# d1-mini-onboard.net
KiCad netlist of a schematic drawn in EAGLE
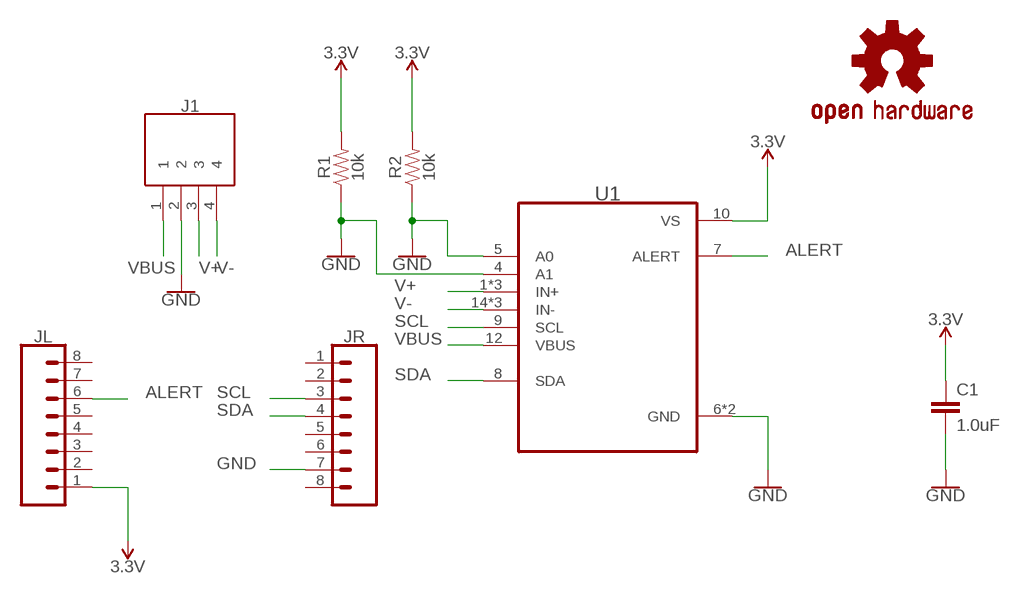
[diagram p0: schematic, sheet 1]

(export (version "E")
  (design (tool "Eeschema 10.0.6"))
  (components
    (comp (ref "C1")
      (value "1.0uF")
      (footprint "eagle-import:1206")
      (libsource (lib "eagle-import") (part "1.0UF-1206-50V-10%"))
    )
    (comp (ref "J1")
      (value "282834-4")
      (footprint "eagle-import:2828344")
      (fields (field (name "MOUSER_PART_NUMBER") "571-282834-4"))
      (libsource (lib "eagle-import") (part "282834-4"))
    )
    (comp (ref "JL")
      (value "CONN_08NO_SILK_FEMALE_PTH")
      (footprint "eagle-import:1X08_NO_SILK")
      (libsource (lib "eagle-import") (part "CONN_08NO_SILK_FEMALE_PTH"))
    )
    (comp (ref "JR")
      (value "CONN_08NO_SILK_FEMALE_PTH")
      (footprint "eagle-import:1X08_NO_SILK")
      (libsource (lib "eagle-import") (part "CONN_08NO_SILK_FEMALE_PTH"))
    )
    (comp (ref "LOGO1")
      (value "OSHW-LOGOS")
      (footprint "eagle-import:OSHW-LOGO-S")
      (libsource (lib "eagle-import") (part "OSHW-LOGOS"))
    )
    (comp (ref "R1")
      (value "10k")
      (footprint "eagle-import:1206")
      (libsource (lib "eagle-import") (part "RESISTOR1206"))
    )
    (comp (ref "R2")
      (value "10k")
      (footprint "eagle-import:1206")
      (libsource (lib "eagle-import") (part "RESISTOR1206"))
    )
    (comp (ref "U1")
      (value "INA260AIPWR")
      (footprint "eagle-import:SOP65P640X120-16N")
      (fields (field (name "MF") "Texas Instruments"))
      (libsource (lib "eagle-import") (part "INA260AIPWR"))
    )
  )
  (nets
    (net (code "1") (name "/ALERT") (class "Default")
      (node (ref "JL") (pin "6") (pinfunction "6_6") (pintype "passive"))
      (node (ref "U1") (pin "7") (pinfunction "ALERT_7") (pintype "output"))
    )
    (net (code "2") (name "/SCL") (class "Default")
      (node (ref "JR") (pin "3") (pinfunction "3_3") (pintype "passive"))
      (node (ref "U1") (pin "9") (pinfunction "SCL_9") (pintype "input"))
    )
    (net (code "3") (name "/SDA") (class "Default")
      (node (ref "JR") (pin "4") (pinfunction "4_4") (pintype "passive"))
      (node (ref "U1") (pin "8") (pinfunction "SDA_8") (pintype "bidirectional"))
    )
    (net (code "4") (name "/V+") (class "Default")
      (node (ref "J1") (pin "3") (pinfunction "3_3") (pintype "bidirectional"))
      (node (ref "U1") (pin "1") (pinfunction "IN+_1") (pintype "input"))
      (node (ref "U1") (pin "2") (pinfunction "IN+_2") (pintype "input"))
      (node (ref "U1") (pin "3") (pinfunction "IN+_3") (pintype "input"))
    )
    (net (code "5") (name "/V-") (class "Default")
      (node (ref "J1") (pin "4") (pinfunction "4_4") (pintype "bidirectional"))
      (node (ref "U1") (pin "14") (pinfunction "IN-_14") (pintype "input"))
      (node (ref "U1") (pin "15") (pinfunction "IN-_15") (pintype "input"))
      (node (ref "U1") (pin "16") (pinfunction "IN-_16") (pintype "input"))
    )
    (net (code "6") (name "/VBUS") (class "Default")
      (node (ref "J1") (pin "1") (pinfunction "1_1") (pintype "bidirectional"))
      (node (ref "U1") (pin "12") (pinfunction "VBUS_12") (pintype "input"))
    )
    (net (code "7") (name "3.3V") (class "Default")
      (node (ref "C1") (pin "1") (pinfunction "1_1") (pintype "passive"))
      (node (ref "JL") (pin "1") (pinfunction "1_1") (pintype "passive"))
      (node (ref "R1") (pin "2") (pinfunction "2_2") (pintype "passive"))
      (node (ref "R2") (pin "2") (pinfunction "2_2") (pintype "passive"))
      (node (ref "U1") (pin "10") (pinfunction "VS_10") (pintype "power_in"))
    )
    (net (code "8") (name "GND") (class "Default")
      (node (ref "C1") (pin "2") (pinfunction "2_2") (pintype "passive"))
      (node (ref "J1") (pin "2") (pinfunction "2_2") (pintype "bidirectional"))
      (node (ref "JR") (pin "7") (pinfunction "7_7") (pintype "passive"))
      (node (ref "R1") (pin "1") (pinfunction "1_1") (pintype "passive"))
      (node (ref "R2") (pin "1") (pinfunction "1_1") (pintype "passive"))
      (node (ref "U1") (pin "11") (pinfunction "GND_11") (pintype "power_in"))
      (node (ref "U1") (pin "4") (pinfunction "A1_4") (pintype "input"))
      (node (ref "U1") (pin "5") (pinfunction "A0_5") (pintype "input"))
      (node (ref "U1") (pin "6") (pinfunction "GND_6") (pintype "power_in"))
    )
    (net (code "9") (name "unconnected-(JL-Pad2)") (class "Default")
      (node (ref "JL") (pin "2") (pinfunction "2_2") (pintype "passive"))
    )
    (net (code "10") (name "unconnected-(JL-Pad3)") (class "Default")
      (node (ref "JL") (pin "3") (pinfunction "3_3") (pintype "passive"))
    )
    (net (code "11") (name "unconnected-(JL-Pad4)") (class "Default")
      (node (ref "JL") (pin "4") (pinfunction "4_4") (pintype "passive"))
    )
    (net (code "12") (name "unconnected-(JL-Pad5)") (class "Default")
      (node (ref "JL") (pin "5") (pinfunction "5_5") (pintype "passive"))
    )
    (net (code "13") (name "unconnected-(JL-Pad7)") (class "Default")
      (node (ref "JL") (pin "7") (pinfunction "7_7") (pintype "passive"))
    )
    (net (code "14") (name "unconnected-(JL-Pad8)") (class "Default")
      (node (ref "JL") (pin "8") (pinfunction "8_8") (pintype "passive"))
    )
    (net (code "15") (name "unconnected-(JR-Pad1)") (class "Default")
      (node (ref "JR") (pin "1") (pinfunction "1_1") (pintype "passive"))
    )
    (net (code "16") (name "unconnected-(JR-Pad2)") (class "Default")
      (node (ref "JR") (pin "2") (pinfunction "2_2") (pintype "passive"))
    )
    (net (code "17") (name "unconnected-(JR-Pad5)") (class "Default")
      (node (ref "JR") (pin "5") (pinfunction "5_5") (pintype "passive"))
    )
    (net (code "18") (name "unconnected-(JR-Pad6)") (class "Default")
      (node (ref "JR") (pin "6") (pinfunction "6_6") (pintype "passive"))
    )
    (net (code "19") (name "unconnected-(JR-Pad8)") (class "Default")
      (node (ref "JR") (pin "8") (pinfunction "8_8") (pintype "passive"))
    )
  )
)
